# Balun_Board_mb.net
KiCad netlist of a schematic drawn in EAGLE
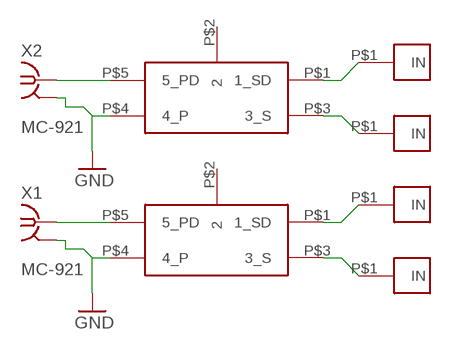
[diagram p0: schematic, sheet 1]

(export (version "E")
  (design (tool "Eeschema 10.0.6"))
  (components
    (comp (ref "U$1")
      (value "MABA-007159-000000")
      (footprint "eagle-import:MABA-007159-000000")
      (libsource (lib "eagle-import") (part "MABA-007159-000000"))
    )
    (comp (ref "U$2")
      (value "MABA-007159-000000")
      (footprint "eagle-import:MABA-007159-000000")
      (libsource (lib "eagle-import") (part "MABA-007159-000000"))
    )
    (comp (ref "U$5")
      (value "SMD-WIRE")
      (footprint "eagle-import:SMD-WIRE")
      (libsource (lib "eagle-import") (part "SMD-WIRE"))
    )
    (comp (ref "U$6")
      (value "SMD-WIRE")
      (footprint "eagle-import:SMD-WIRE")
      (libsource (lib "eagle-import") (part "SMD-WIRE"))
    )
    (comp (ref "U$7")
      (value "SMD-WIRE")
      (footprint "eagle-import:SMD-WIRE")
      (libsource (lib "eagle-import") (part "SMD-WIRE"))
    )
    (comp (ref "U$8")
      (value "SMD-WIRE")
      (footprint "eagle-import:SMD-WIRE")
      (libsource (lib "eagle-import") (part "SMD-WIRE"))
    )
    (comp (ref "X1")
      (value "MC-921")
      (footprint "eagle-import:MC-921")
      (libsource (lib "eagle-import") (part "MC-921"))
    )
    (comp (ref "X2")
      (value "MC-921")
      (footprint "eagle-import:MC-921")
      (libsource (lib "eagle-import") (part "MC-921"))
    )
  )
  (nets
    (net (code "1") (name "GND") (class "Default")
      (node (ref "U$1") (pin "P$4") (pinfunction "4_P_P$4") (pintype "bidirectional"))
      (node (ref "U$2") (pin "P$4") (pinfunction "4_P_P$4") (pintype "bidirectional"))
      (node (ref "X1") (pin "2@1") (pinfunction "GND_2@1") (pintype "passive"))
      (node (ref "X1") (pin "2@2") (pinfunction "GND_2@2") (pintype "passive"))
      (node (ref "X2") (pin "2@1") (pinfunction "GND_2@1") (pintype "passive"))
      (node (ref "X2") (pin "2@2") (pinfunction "GND_2@2") (pintype "passive"))
    )
    (net (code "2") (name "Net-(U$1-1_SD)") (class "Default")
      (node (ref "U$1") (pin "P$1") (pinfunction "1_SD_P$1") (pintype "bidirectional"))
      (node (ref "U$5") (pin "P$1") (pinfunction "IN_P$1") (pintype "input"))
    )
    (net (code "3") (name "Net-(U$1-3_S)") (class "Default")
      (node (ref "U$1") (pin "P$3") (pinfunction "3_S_P$3") (pintype "bidirectional"))
      (node (ref "U$6") (pin "P$1") (pinfunction "IN_P$1") (pintype "input"))
    )
    (net (code "4") (name "Net-(U$1-5_PD)") (class "Default")
      (node (ref "U$1") (pin "P$5") (pinfunction "5_PD_P$5") (pintype "bidirectional"))
      (node (ref "X2") (pin "1") (pinfunction "1_1") (pintype "passive"))
    )
    (net (code "5") (name "Net-(U$2-1_SD)") (class "Default")
      (node (ref "U$2") (pin "P$1") (pinfunction "1_SD_P$1") (pintype "bidirectional"))
      (node (ref "U$7") (pin "P$1") (pinfunction "IN_P$1") (pintype "input"))
    )
    (net (code "6") (name "Net-(U$2-3_S)") (class "Default")
      (node (ref "U$2") (pin "P$3") (pinfunction "3_S_P$3") (pintype "bidirectional"))
      (node (ref "U$8") (pin "P$1") (pinfunction "IN_P$1") (pintype "input"))
    )
    (net (code "7") (name "Net-(U$2-5_PD)") (class "Default")
      (node (ref "U$2") (pin "P$5") (pinfunction "5_PD_P$5") (pintype "bidirectional"))
      (node (ref "X1") (pin "1") (pinfunction "1_1") (pintype "passive"))
    )
    (net (code "8") (name "unconnected-(U$1-2-PadP$2)") (class "Default")
      (node (ref "U$1") (pin "P$2") (pinfunction "2_P$2") (pintype "bidirectional"))
    )
    (net (code "9") (name "unconnected-(U$2-2-PadP$2)") (class "Default")
      (node (ref "U$2") (pin "P$2") (pinfunction "2_P$2") (pintype "bidirectional"))
    )
  )
)
